# PSPS_AVNC_SRD_sensors-2020-09-29.net
KiCad netlist of a schematic drawn in EAGLE
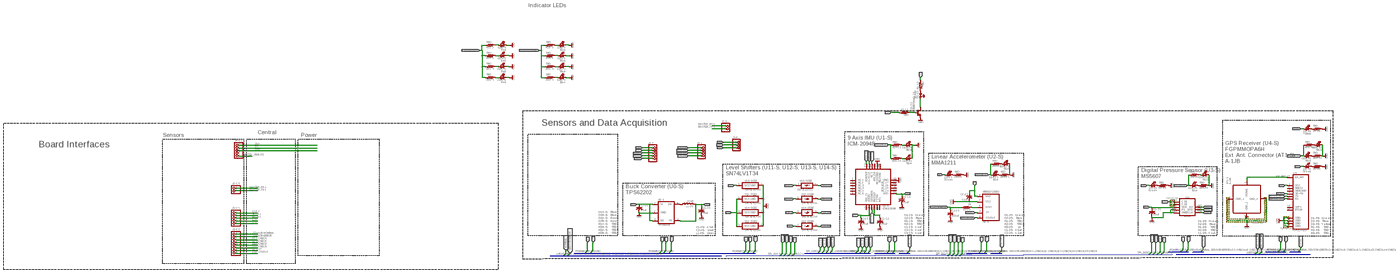
[diagram p0: schematic, sheet 1, overview]
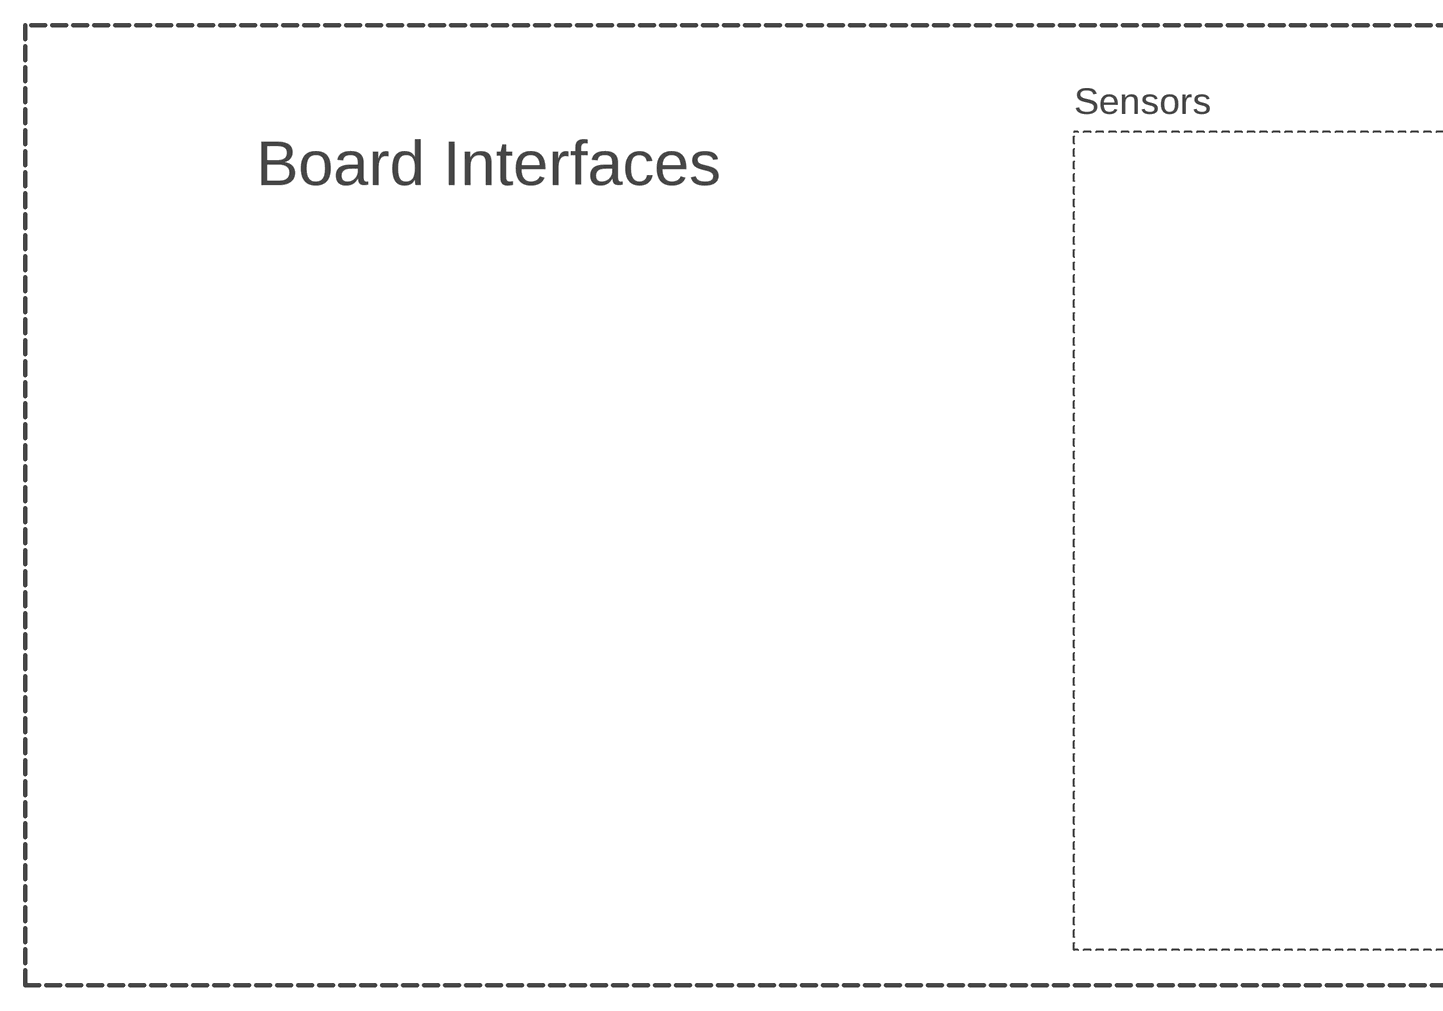
[diagram p1: schematic, sheet 1, part 1 of 4]
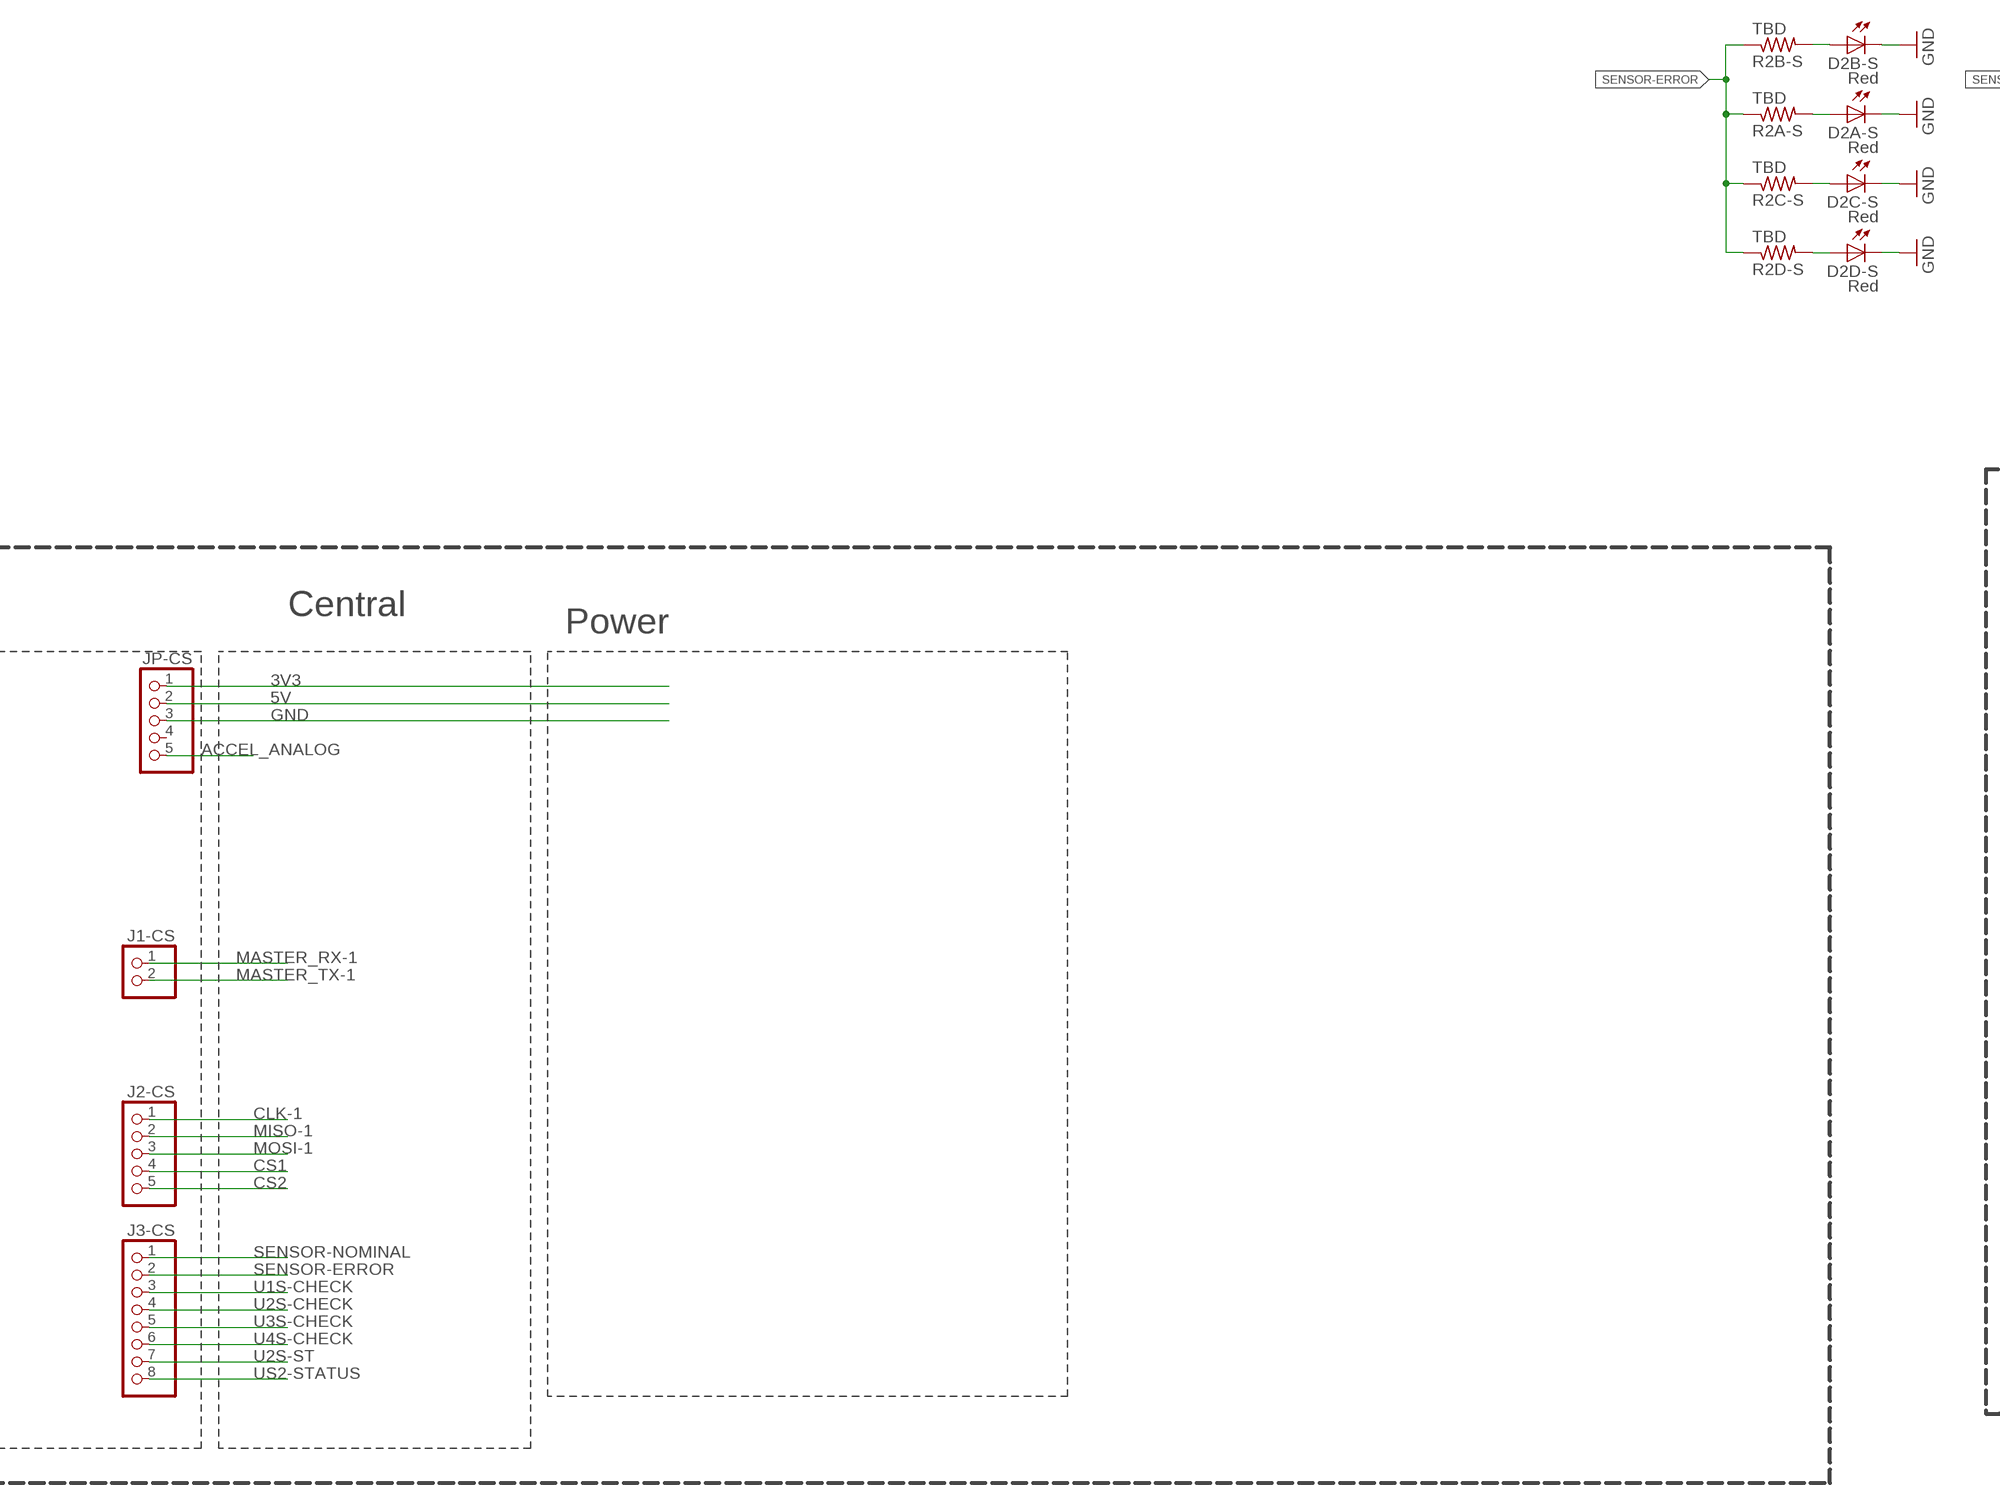
[diagram p2: schematic, sheet 1, part 2 of 4]
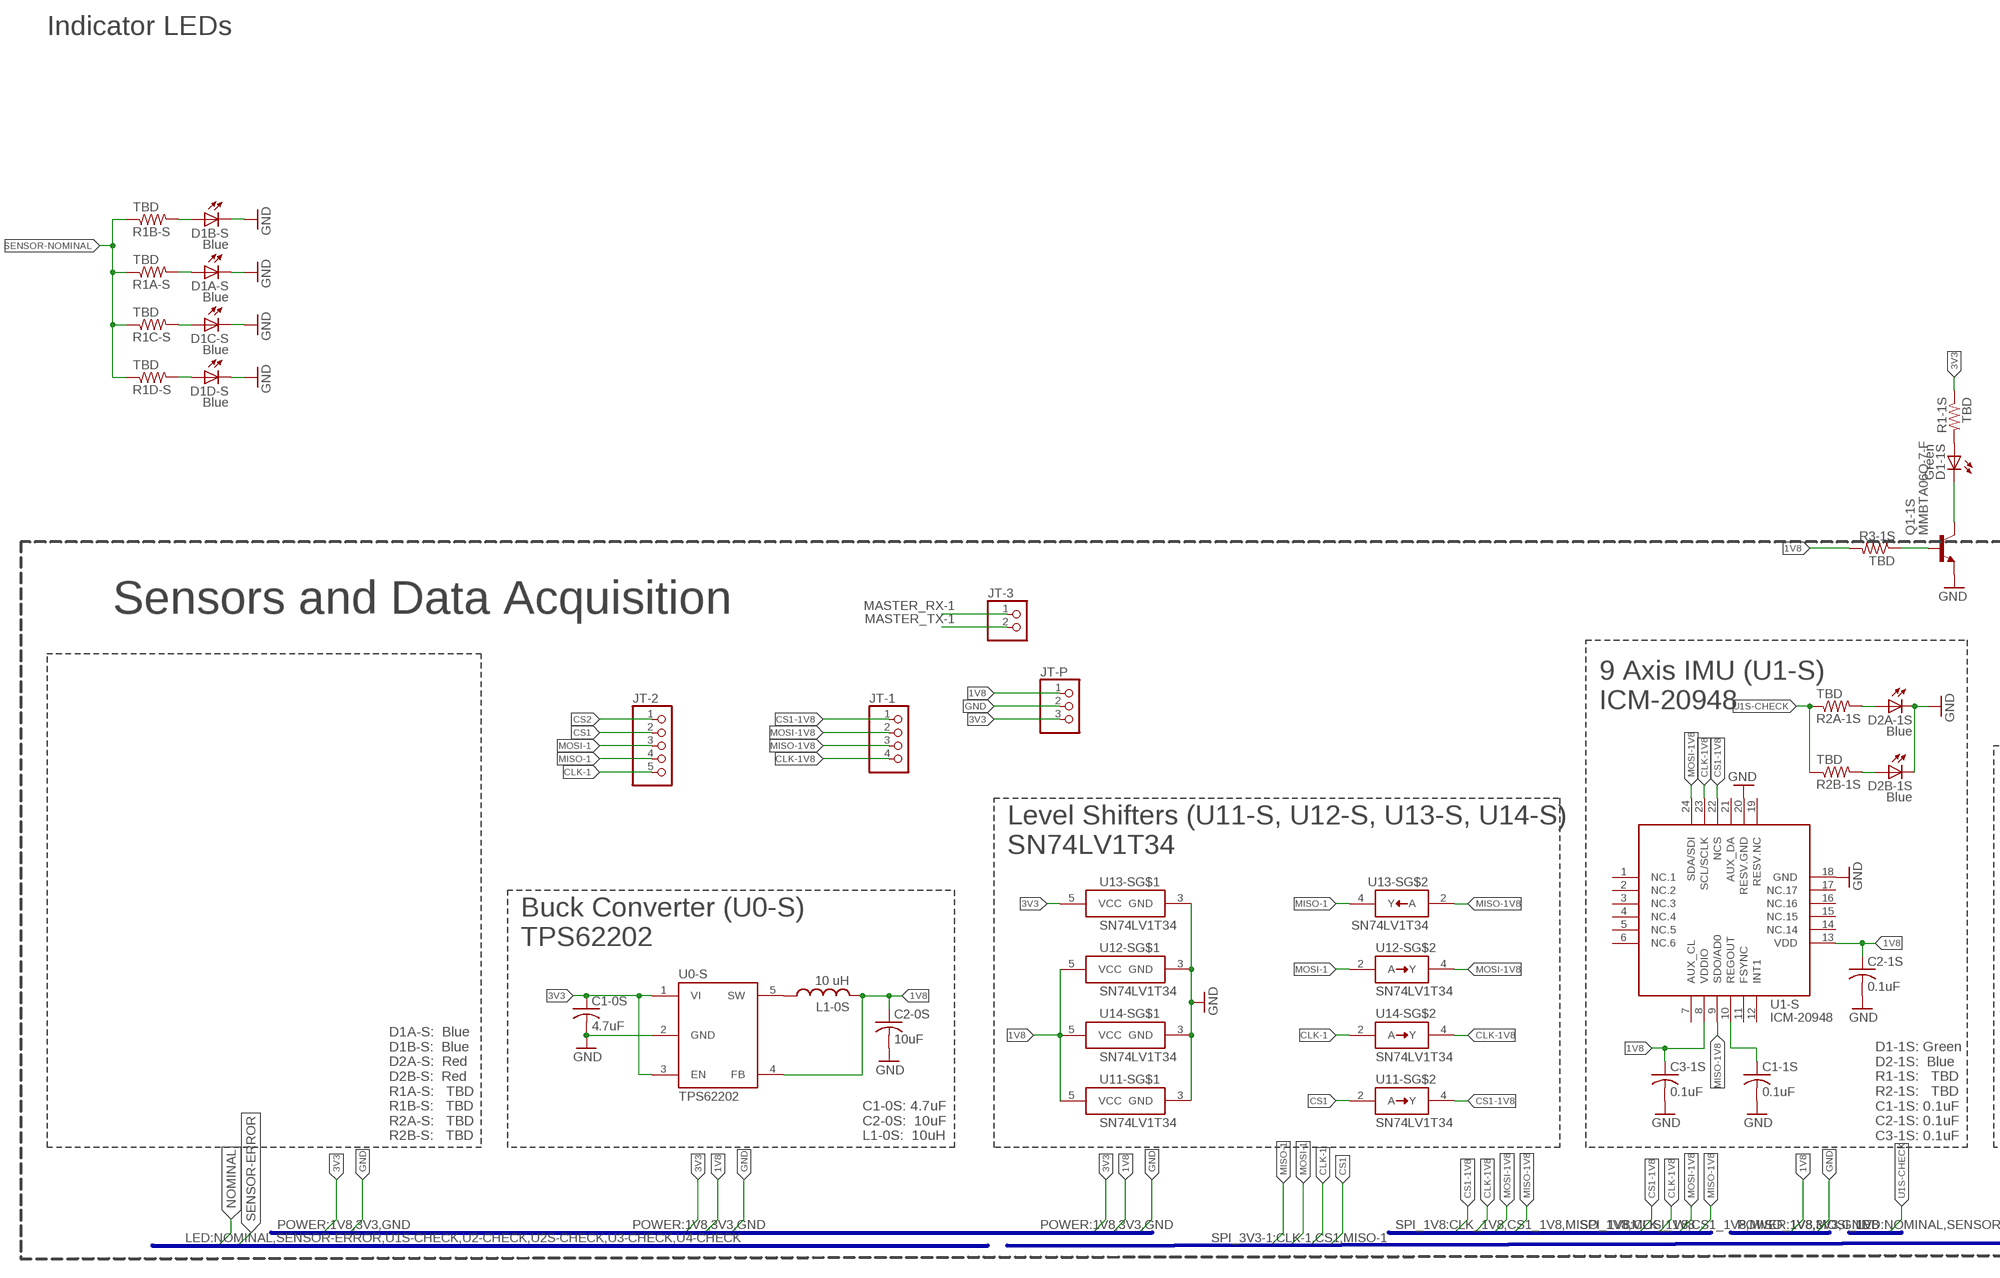
[diagram p3: schematic, sheet 1, part 3 of 4]
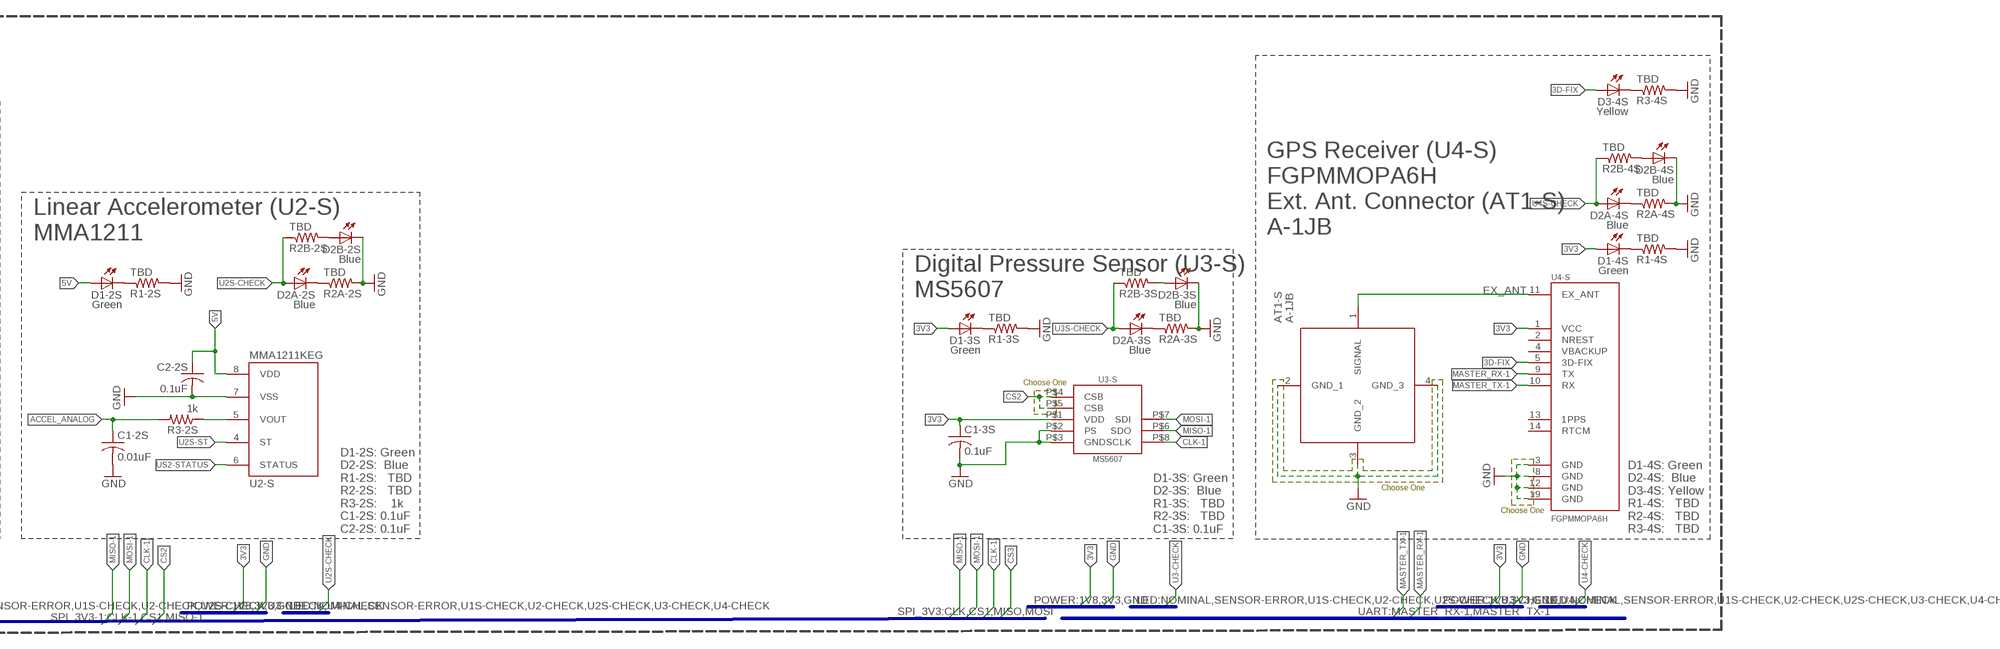
[diagram p4: schematic, sheet 1, part 4 of 4]

(export (version "E")
  (design (tool "Eeschema 10.0.6"))
  (components
    (comp (ref "AT1-S")
      (value "A-1JB")
      (footprint "eagle-import:A1JB")
      (fields (field (name "MOUSER_PART_NUMBER") "523-A-1JB"))
      (libsource (lib "eagle-import") (part "A-1JB"))
    )
    (comp (ref "C1-0S")
      (value "4.7uF")
      (footprint "eagle-import:C0805")
      (libsource (lib "eagle-import") (part "C-USC0805"))
    )
    (comp (ref "C1-1S")
      (value "0.1uF")
      (footprint "eagle-import:C0805")
      (libsource (lib "eagle-import") (part "C-USC0805"))
    )
    (comp (ref "C1-2S")
      (value "0.01uF")
      (footprint "eagle-import:C0805")
      (libsource (lib "eagle-import") (part "C-USC0805"))
    )
    (comp (ref "C1-3S")
      (value "0.1uF")
      (footprint "eagle-import:C0805")
      (libsource (lib "eagle-import") (part "C-USC0805"))
    )
    (comp (ref "C2-0S")
      (value "10uF")
      (footprint "eagle-import:C0805")
      (libsource (lib "eagle-import") (part "C-USC0805"))
    )
    (comp (ref "C2-1S")
      (value "0.1uF")
      (footprint "eagle-import:C0805")
      (libsource (lib "eagle-import") (part "C-USC0805"))
    )
    (comp (ref "C2-2S")
      (value "0.1uF")
      (footprint "eagle-import:C0805")
      (libsource (lib "eagle-import") (part "C-USC0805"))
    )
    (comp (ref "C3-1S")
      (value "0.1uF")
      (footprint "eagle-import:C0805")
      (libsource (lib "eagle-import") (part "C-USC0805"))
    )
    (comp (ref "D1-1S")
      (value "Green")
      (footprint "eagle-import:CHIPLED_0805")
      (libsource (lib "eagle-import") (part "LEDCHIPLED_0805"))
    )
    (comp (ref "D1-2S")
      (value "Green")
      (footprint "eagle-import:CHIPLED_0805")
      (libsource (lib "eagle-import") (part "LEDCHIPLED_0805"))
    )
    (comp (ref "D1-3S")
      (value "Green")
      (footprint "eagle-import:CHIPLED_0805")
      (libsource (lib "eagle-import") (part "LEDCHIPLED_0805"))
    )
    (comp (ref "D1-4S")
      (value "Green")
      (footprint "eagle-import:CHIPLED_0805")
      (libsource (lib "eagle-import") (part "LEDCHIPLED_0805"))
    )
    (comp (ref "D1A-S")
      (value "Blue")
      (footprint "eagle-import:CHIPLED_0805")
      (libsource (lib "eagle-import") (part "LEDCHIPLED_0805"))
    )
    (comp (ref "D1B-S")
      (value "Blue")
      (footprint "eagle-import:CHIPLED_0805")
      (libsource (lib "eagle-import") (part "LEDCHIPLED_0805"))
    )
    (comp (ref "D1C-S")
      (value "Blue")
      (footprint "eagle-import:CHIPLED_0805")
      (libsource (lib "eagle-import") (part "LEDCHIPLED_0805"))
    )
    (comp (ref "D1D-S")
      (value "Blue")
      (footprint "eagle-import:CHIPLED_0805")
      (libsource (lib "eagle-import") (part "LEDCHIPLED_0805"))
    )
    (comp (ref "D2A-1S")
      (value "Blue")
      (footprint "eagle-import:CHIPLED_0805")
      (libsource (lib "eagle-import") (part "LEDCHIPLED_0805"))
    )
    (comp (ref "D2A-2S")
      (value "Blue")
      (footprint "eagle-import:CHIPLED_0805")
      (libsource (lib "eagle-import") (part "LEDCHIPLED_0805"))
    )
    (comp (ref "D2A-3S")
      (value "Blue")
      (footprint "eagle-import:CHIPLED_0805")
      (libsource (lib "eagle-import") (part "LEDCHIPLED_0805"))
    )
    (comp (ref "D2A-4S")
      (value "Blue")
      (footprint "eagle-import:CHIPLED_0805")
      (libsource (lib "eagle-import") (part "LEDCHIPLED_0805"))
    )
    (comp (ref "D2A-S")
      (value "Red")
      (footprint "eagle-import:CHIPLED_0805")
      (libsource (lib "eagle-import") (part "LEDCHIPLED_0805"))
    )
    (comp (ref "D2B-1S")
      (value "Blue")
      (footprint "eagle-import:CHIPLED_0805")
      (libsource (lib "eagle-import") (part "LEDCHIPLED_0805"))
    )
    (comp (ref "D2B-2S")
      (value "Blue")
      (footprint "eagle-import:CHIPLED_0805")
      (libsource (lib "eagle-import") (part "LEDCHIPLED_0805"))
    )
    (comp (ref "D2B-3S")
      (value "Blue")
      (footprint "eagle-import:CHIPLED_0805")
      (libsource (lib "eagle-import") (part "LEDCHIPLED_0805"))
    )
    (comp (ref "D2B-4S")
      (value "Blue")
      (footprint "eagle-import:CHIPLED_0805")
      (libsource (lib "eagle-import") (part "LEDCHIPLED_0805"))
    )
    (comp (ref "D2B-S")
      (value "Red")
      (footprint "eagle-import:CHIPLED_0805")
      (libsource (lib "eagle-import") (part "LEDCHIPLED_0805"))
    )
    (comp (ref "D2C-S")
      (value "Red")
      (footprint "eagle-import:CHIPLED_0805")
      (libsource (lib "eagle-import") (part "LEDCHIPLED_0805"))
    )
    (comp (ref "D2D-S")
      (value "Red")
      (footprint "eagle-import:CHIPLED_0805")
      (libsource (lib "eagle-import") (part "LEDCHIPLED_0805"))
    )
    (comp (ref "D3-4S")
      (value "Yellow")
      (footprint "eagle-import:CHIPLED_0805")
      (libsource (lib "eagle-import") (part "LEDCHIPLED_0805"))
    )
    (comp (ref "J1-CS")
      (value "PINHD-1X2")
      (footprint "eagle-import:1X02")
      (libsource (lib "eagle-import") (part "PINHD-1X2"))
    )
    (comp (ref "J2-CS")
      (value "PINHD-1X5")
      (footprint "eagle-import:1X05")
      (libsource (lib "eagle-import") (part "PINHD-1X5"))
    )
    (comp (ref "J3-CS")
      (value "PINHD-1X8")
      (footprint "eagle-import:1X08")
      (libsource (lib "eagle-import") (part "PINHD-1X8"))
    )
    (comp (ref "JP-CS")
      (value "PINHD-1X5")
      (footprint "eagle-import:1X05")
      (libsource (lib "eagle-import") (part "PINHD-1X5"))
    )
    (comp (ref "JT-1")
      (value "PINHD-1X4")
      (footprint "eagle-import:1X04")
      (libsource (lib "eagle-import") (part "PINHD-1X4"))
    )
    (comp (ref "JT-2")
      (value "PINHD-1X5")
      (footprint "eagle-import:1X05")
      (libsource (lib "eagle-import") (part "PINHD-1X5"))
    )
    (comp (ref "JT-3")
      (value "PINHD-1X2")
      (footprint "eagle-import:1X02")
      (libsource (lib "eagle-import") (part "PINHD-1X2"))
    )
    (comp (ref "JT-P")
      (value "PINHD-1X3")
      (footprint "eagle-import:1X03")
      (libsource (lib "eagle-import") (part "PINHD-1X3"))
    )
    (comp (ref "L1-0S")
      (value "10 uH")
      (footprint "eagle-import:L1812")
      (libsource (lib "eagle-import") (part "L-USL1812"))
    )
    (comp (ref "Q1-1S")
      (value "MMBTA06Q-7-F")
      (footprint "eagle-import:SOT23")
      (libsource (lib "eagle-import") (part "NPN_TRANSISTOR"))
    )
    (comp (ref "R1-1S")
      (value "TBD")
      (footprint "eagle-import:R0805")
      (libsource (lib "eagle-import") (part "R-US_R0805"))
    )
    (comp (ref "R1-2S")
      (value "TBD")
      (footprint "eagle-import:R0805")
      (libsource (lib "eagle-import") (part "R-US_R0805"))
    )
    (comp (ref "R1-3S")
      (value "TBD")
      (footprint "eagle-import:R0805")
      (libsource (lib "eagle-import") (part "R-US_R0805"))
    )
    (comp (ref "R1-4S")
      (value "TBD")
      (footprint "eagle-import:R0805")
      (libsource (lib "eagle-import") (part "R-US_R0805"))
    )
    (comp (ref "R1A-S")
      (value "TBD")
      (footprint "eagle-import:R0805")
      (libsource (lib "eagle-import") (part "R-US_R0805"))
    )
    (comp (ref "R1B-S")
      (value "TBD")
      (footprint "eagle-import:R0805")
      (libsource (lib "eagle-import") (part "R-US_R0805"))
    )
    (comp (ref "R1C-S")
      (value "TBD")
      (footprint "eagle-import:R0805")
      (libsource (lib "eagle-import") (part "R-US_R0805"))
    )
    (comp (ref "R1D-S")
      (value "TBD")
      (footprint "eagle-import:R0805")
      (libsource (lib "eagle-import") (part "R-US_R0805"))
    )
    (comp (ref "R2A-1S")
      (value "TBD")
      (footprint "eagle-import:R0805")
      (libsource (lib "eagle-import") (part "R-US_R0805"))
    )
    (comp (ref "R2A-2S")
      (value "TBD")
      (footprint "eagle-import:R0805")
      (libsource (lib "eagle-import") (part "R-US_R0805"))
    )
    (comp (ref "R2A-3S")
      (value "TBD")
      (footprint "eagle-import:R0805")
      (libsource (lib "eagle-import") (part "R-US_R0805"))
    )
    (comp (ref "R2A-4S")
      (value "TBD")
      (footprint "eagle-import:R0805")
      (libsource (lib "eagle-import") (part "R-US_R0805"))
    )
    (comp (ref "R2A-S")
      (value "TBD")
      (footprint "eagle-import:R0805")
      (libsource (lib "eagle-import") (part "R-US_R0805"))
    )
    (comp (ref "R2B-1S")
      (value "TBD")
      (footprint "eagle-import:R0805")
      (libsource (lib "eagle-import") (part "R-US_R0805"))
    )
    (comp (ref "R2B-2S")
      (value "TBD")
      (footprint "eagle-import:R0805")
      (libsource (lib "eagle-import") (part "R-US_R0805"))
    )
    (comp (ref "R2B-3S")
      (value "TBD")
      (footprint "eagle-import:R0805")
      (libsource (lib "eagle-import") (part "R-US_R0805"))
    )
    (comp (ref "R2B-4S")
      (value "TBD")
      (footprint "eagle-import:R0805")
      (libsource (lib "eagle-import") (part "R-US_R0805"))
    )
    (comp (ref "R2B-S")
      (value "TBD")
      (footprint "eagle-import:R0805")
      (libsource (lib "eagle-import") (part "R-US_R0805"))
    )
    (comp (ref "R2C-S")
      (value "TBD")
      (footprint "eagle-import:R0805")
      (libsource (lib "eagle-import") (part "R-US_R0805"))
    )
    (comp (ref "R2D-S")
      (value "TBD")
      (footprint "eagle-import:R0805")
      (libsource (lib "eagle-import") (part "R-US_R0805"))
    )
    (comp (ref "R3-1S")
      (value "TBD")
      (footprint "eagle-import:R0805")
      (libsource (lib "eagle-import") (part "R-US_R0805"))
    )
    (comp (ref "R3-2S")
      (value "1k")
      (footprint "eagle-import:R0805")
      (libsource (lib "eagle-import") (part "R-US_R0805"))
    )
    (comp (ref "R3-4S")
      (value "TBD")
      (footprint "eagle-import:R0805")
      (libsource (lib "eagle-import") (part "R-US_R0805"))
    )
    (comp (ref "U0-S")
      (value "TPS62202")
      (footprint "eagle-import:SOT95P280X145-5")
      (libsource (lib "eagle-import") (part "TPS62202"))
    )
    (comp (ref "U1-S")
      (value "ICM-20948")
      (footprint "eagle-import:QFN40P300X300X105-25T159X175")
      (libsource (lib "eagle-import") (part "ICM-20948"))
    )
    (comp (ref "U2-S")
      (value "MMA1211KEG")
      (footprint "eagle-import:SOIC127P1041X355-16N")
      (libsource (lib "eagle-import") (part "MMA1211KEG"))
    )
    (comp (ref "U3-S")
      (value "MS5607")
      (footprint "eagle-import:MS5607")
      (libsource (lib "eagle-import") (part "MS5607"))
    )
    (comp (ref "U4-S")
      (value "FGPMMOPA6H")
      (footprint "eagle-import:SOIC127P1800X470-20N")
      (libsource (lib "eagle-import") (part "FGPMMOPA6H"))
    )
    (comp (ref "U11-S")
      (value "SN74LV1T34")
      (footprint "eagle-import:SOT65P210X110-5")
      (libsource (lib "eagle-import") (part "SN74LV1T34"))
    )
    (comp (ref "U12-S")
      (value "SN74LV1T34")
      (footprint "eagle-import:SOT65P210X110-5")
      (libsource (lib "eagle-import") (part "SN74LV1T34"))
    )
    (comp (ref "U13-S")
      (value "SN74LV1T34")
      (footprint "eagle-import:SOT65P210X110-5")
      (libsource (lib "eagle-import") (part "SN74LV1T34"))
    )
    (comp (ref "U14-S")
      (value "SN74LV1T34")
      (footprint "eagle-import:SOT65P210X110-5")
      (libsource (lib "eagle-import") (part "SN74LV1T34"))
    )
  )
  (nets
    (net (code "13") (name "/EX_ANT") (class "Default")
      (node (ref "AT1-S") (pin "1") (pinfunction "SIGNAL_1") (pintype "bidirectional"))
      (node (ref "U4-S") (pin "11") (pinfunction "EX_ANT_11") (pintype "bidirectional"))
    )
    (net (code "20") (name "1V8") (class "Default")
      (node (ref "C2-0S") (pin "1") (pinfunction "1_1") (pintype "passive"))
      (node (ref "C2-1S") (pin "1") (pinfunction "1_1") (pintype "passive"))
      (node (ref "C3-1S") (pin "1") (pinfunction "1_1") (pintype "passive"))
      (node (ref "JT-P") (pin "1") (pinfunction "1_1") (pintype "passive"))
      (node (ref "L1-0S") (pin "2") (pinfunction "2_2") (pintype "passive"))
      (node (ref "R3-1S") (pin "2") (pinfunction "2_2") (pintype "passive"))
      (node (ref "U0-S") (pin "4") (pinfunction "FB_4") (pintype "bidirectional"))
      (node (ref "U1-S") (pin "13") (pinfunction "VDD_13") (pintype "bidirectional"))
      (node (ref "U1-S") (pin "8") (pinfunction "VDDIO_8") (pintype "bidirectional"))
      (node (ref "U11-S") (pin "5") (pinfunction "VCC_5") (pintype "bidirectional"))
      (node (ref "U12-S") (pin "5") (pinfunction "VCC_5") (pintype "bidirectional"))
      (node (ref "U14-S") (pin "5") (pinfunction "VCC_5") (pintype "bidirectional"))
    )
    (net (code "21") (name "3D-FIX") (class "Default")
      (node (ref "D3-4S") (pin "A") (pinfunction "A_A") (pintype "passive"))
      (node (ref "U4-S") (pin "5") (pinfunction "3D-FIX_5") (pintype "bidirectional"))
    )
    (net (code "22") (name "3V3") (class "Default")
      (node (ref "C1-0S") (pin "1") (pinfunction "1_1") (pintype "passive"))
      (node (ref "C1-3S") (pin "1") (pinfunction "1_1") (pintype "passive"))
      (node (ref "D1-3S") (pin "A") (pinfunction "A_A") (pintype "passive"))
      (node (ref "D1-4S") (pin "A") (pinfunction "A_A") (pintype "passive"))
      (node (ref "JP-CS") (pin "1") (pinfunction "1_1") (pintype "passive"))
      (node (ref "JT-P") (pin "3") (pinfunction "3_3") (pintype "passive"))
      (node (ref "R1-1S") (pin "1") (pinfunction "1_1") (pintype "passive"))
      (node (ref "U0-S") (pin "1") (pinfunction "VI_1") (pintype "bidirectional"))
      (node (ref "U0-S") (pin "3") (pinfunction "EN_3") (pintype "bidirectional"))
      (node (ref "U13-S") (pin "5") (pinfunction "VCC_5") (pintype "bidirectional"))
      (node (ref "U3-S") (pin "P$1") (pinfunction "VDD_P$1") (pintype "bidirectional"))
      (node (ref "U4-S") (pin "1") (pinfunction "VCC_1") (pintype "bidirectional"))
    )
    (net (code "23") (name "5V") (class "Default")
      (node (ref "C2-2S") (pin "1") (pinfunction "1_1") (pintype "passive"))
      (node (ref "D1-2S") (pin "A") (pinfunction "A_A") (pintype "passive"))
      (node (ref "JP-CS") (pin "2") (pinfunction "2_2") (pintype "passive"))
      (node (ref "U2-S") (pin "8") (pinfunction "VDD_8") (pintype "bidirectional"))
    )
    (net (code "24") (name "ACCEL_ANALOG") (class "Default")
      (node (ref "C1-2S") (pin "1") (pinfunction "1_1") (pintype "passive"))
      (node (ref "JP-CS") (pin "5") (pinfunction "5_5") (pintype "passive"))
      (node (ref "R3-2S") (pin "2") (pinfunction "2_2") (pintype "passive"))
    )
    (net (code "25") (name "CLK-1") (class "Default")
      (node (ref "J2-CS") (pin "1") (pinfunction "1_1") (pintype "passive"))
      (node (ref "JT-2") (pin "5") (pinfunction "5_5") (pintype "passive"))
      (node (ref "U14-S") (pin "2") (pinfunction "A_2") (pintype "bidirectional"))
      (node (ref "U3-S") (pin "P$8") (pinfunction "SCLK_P$8") (pintype "bidirectional"))
    )
    (net (code "26") (name "CLK-1V8") (class "Default")
      (node (ref "JT-1") (pin "4") (pinfunction "4_4") (pintype "passive"))
      (node (ref "U1-S") (pin "23") (pinfunction "SCL/SCLK_23") (pintype "bidirectional"))
      (node (ref "U14-S") (pin "4") (pinfunction "Y_4") (pintype "bidirectional"))
    )
    (net (code "27") (name "CS1") (class "Default")
      (node (ref "J2-CS") (pin "4") (pinfunction "4_4") (pintype "passive"))
      (node (ref "JT-2") (pin "2") (pinfunction "2_2") (pintype "passive"))
      (node (ref "U11-S") (pin "2") (pinfunction "A_2") (pintype "bidirectional"))
    )
    (net (code "28") (name "CS1-1V8") (class "Default")
      (node (ref "JT-1") (pin "1") (pinfunction "1_1") (pintype "passive"))
      (node (ref "U1-S") (pin "22") (pinfunction "NCS_22") (pintype "bidirectional"))
      (node (ref "U11-S") (pin "4") (pinfunction "Y_4") (pintype "bidirectional"))
    )
    (net (code "29") (name "CS2") (class "Default")
      (node (ref "J2-CS") (pin "5") (pinfunction "5_5") (pintype "passive"))
      (node (ref "JT-2") (pin "1") (pinfunction "1_1") (pintype "passive"))
      (node (ref "U3-S") (pin "P$4") (pinfunction "CSB_P$4") (pintype "bidirectional"))
      (node (ref "U3-S") (pin "P$5") (pinfunction "CSB_P$5") (pintype "bidirectional"))
    )
    (net (code "31") (name "GND") (class "Default")
      (node (ref "AT1-S") (pin "2") (pinfunction "GND_1_2") (pintype "bidirectional"))
      (node (ref "AT1-S") (pin "3") (pinfunction "GND_2_3") (pintype "bidirectional"))
      (node (ref "AT1-S") (pin "4") (pinfunction "GND_3_4") (pintype "bidirectional"))
      (node (ref "C1-0S") (pin "2") (pinfunction "2_2") (pintype "passive"))
      (node (ref "C1-1S") (pin "2") (pinfunction "2_2") (pintype "passive"))
      (node (ref "C1-2S") (pin "2") (pinfunction "2_2") (pintype "passive"))
      (node (ref "C1-3S") (pin "2") (pinfunction "2_2") (pintype "passive"))
      (node (ref "C2-0S") (pin "2") (pinfunction "2_2") (pintype "passive"))
      (node (ref "C2-1S") (pin "2") (pinfunction "2_2") (pintype "passive"))
      (node (ref "C2-2S") (pin "2") (pinfunction "2_2") (pintype "passive"))
      (node (ref "C3-1S") (pin "2") (pinfunction "2_2") (pintype "passive"))
      (node (ref "D1A-S") (pin "C") (pinfunction "C_C") (pintype "passive"))
      (node (ref "D1B-S") (pin "C") (pinfunction "C_C") (pintype "passive"))
      (node (ref "D1C-S") (pin "C") (pinfunction "C_C") (pintype "passive"))
      (node (ref "D1D-S") (pin "C") (pinfunction "C_C") (pintype "passive"))
      (node (ref "D2A-1S") (pin "C") (pinfunction "C_C") (pintype "passive"))
      (node (ref "D2A-S") (pin "C") (pinfunction "C_C") (pintype "passive"))
      (node (ref "D2B-1S") (pin "C") (pinfunction "C_C") (pintype "passive"))
      (node (ref "D2B-2S") (pin "C") (pinfunction "C_C") (pintype "passive"))
      (node (ref "D2B-3S") (pin "C") (pinfunction "C_C") (pintype "passive"))
      (node (ref "D2B-4S") (pin "C") (pinfunction "C_C") (pintype "passive"))
      (node (ref "D2B-S") (pin "C") (pinfunction "C_C") (pintype "passive"))
      (node (ref "D2C-S") (pin "C") (pinfunction "C_C") (pintype "passive"))
      (node (ref "D2D-S") (pin "C") (pinfunction "C_C") (pintype "passive"))
      (node (ref "JP-CS") (pin "3") (pinfunction "3_3") (pintype "passive"))
      (node (ref "JT-P") (pin "2") (pinfunction "2_2") (pintype "passive"))
      (node (ref "Q1-1S") (pin "3") (pinfunction "E_3") (pintype "passive"))
      (node (ref "R1-2S") (pin "2") (pinfunction "2_2") (pintype "passive"))
      (node (ref "R1-3S") (pin "2") (pinfunction "2_2") (pintype "passive"))
      (node (ref "R1-4S") (pin "2") (pinfunction "2_2") (pintype "passive"))
      (node (ref "R2A-2S") (pin "2") (pinfunction "2_2") (pintype "passive"))
      (node (ref "R2A-3S") (pin "2") (pinfunction "2_2") (pintype "passive"))
      (node (ref "R2A-4S") (pin "2") (pinfunction "2_2") (pintype "passive"))
      (node (ref "R3-4S") (pin "2") (pinfunction "2_2") (pintype "passive"))
      (node (ref "U0-S") (pin "2") (pinfunction "GND_2") (pintype "bidirectional"))
      (node (ref "U1-S") (pin "18") (pinfunction "GND_18") (pintype "bidirectional"))
      (node (ref "U1-S") (pin "20") (pinfunction "RESV.GND_20") (pintype "bidirectional"))
      (node (ref "U11-S") (pin "3") (pinfunction "GND_3") (pintype "bidirectional"))
      (node (ref "U12-S") (pin "3") (pinfunction "GND_3") (pintype "bidirectional"))
      (node (ref "U13-S") (pin "3") (pinfunction "GND_3") (pintype "bidirectional"))
      (node (ref "U14-S") (pin "3") (pinfunction "GND_3") (pintype "bidirectional"))
      (node (ref "U2-S") (pin "7") (pinfunction "VSS_7") (pintype "bidirectional"))
      (node (ref "U3-S") (pin "P$2") (pinfunction "PS_P$2") (pintype "bidirectional"))
      (node (ref "U3-S") (pin "P$3") (pinfunction "GND_P$3") (pintype "bidirectional"))
      (node (ref "U4-S") (pin "12") (pinfunction "GND_12") (pintype "bidirectional"))
      (node (ref "U4-S") (pin "19") (pinfunction "GND_19") (pintype "bidirectional"))
      (node (ref "U4-S") (pin "3") (pinfunction "GND_3") (pintype "bidirectional"))
      (node (ref "U4-S") (pin "8") (pinfunction "GND_8") (pintype "bidirectional"))
    )
    (net (code "32") (name "MASTER_RX-1") (class "Default")
      (node (ref "J1-CS") (pin "1") (pinfunction "1_1") (pintype "passive"))
      (node (ref "JT-3") (pin "1") (pinfunction "1_1") (pintype "passive"))
      (node (ref "U4-S") (pin "9") (pinfunction "TX_9") (pintype "bidirectional"))
    )
    (net (code "33") (name "MASTER_TX-1") (class "Default")
      (node (ref "J1-CS") (pin "2") (pinfunction "2_2") (pintype "passive"))
      (node (ref "JT-3") (pin "2") (pinfunction "2_2") (pintype "passive"))
      (node (ref "U4-S") (pin "10") (pinfunction "RX_10") (pintype "bidirectional"))
    )
    (net (code "34") (name "MISO-1") (class "Default")
      (node (ref "J2-CS") (pin "2") (pinfunction "2_2") (pintype "passive"))
      (node (ref "JT-2") (pin "4") (pinfunction "4_4") (pintype "passive"))
      (node (ref "U13-S") (pin "4") (pinfunction "Y_4") (pintype "bidirectional"))
      (node (ref "U3-S") (pin "P$6") (pinfunction "SDO_P$6") (pintype "bidirectional"))
    )
    (net (code "35") (name "MISO-1V8") (class "Default")
      (node (ref "JT-1") (pin "3") (pinfunction "3_3") (pintype "passive"))
      (node (ref "U1-S") (pin "9") (pinfunction "SDO/AD0_9") (pintype "bidirectional"))
      (node (ref "U13-S") (pin "2") (pinfunction "A_2") (pintype "bidirectional"))
    )
    (net (code "36") (name "MOSI-1") (class "Default")
      (node (ref "J2-CS") (pin "3") (pinfunction "3_3") (pintype "passive"))
      (node (ref "JT-2") (pin "3") (pinfunction "3_3") (pintype "passive"))
      (node (ref "U12-S") (pin "2") (pinfunction "A_2") (pintype "bidirectional"))
      (node (ref "U3-S") (pin "P$7") (pinfunction "SDI_P$7") (pintype "bidirectional"))
    )
    (net (code "37") (name "MOSI-1V8") (class "Default")
      (node (ref "JT-1") (pin "2") (pinfunction "2_2") (pintype "passive"))
      (node (ref "U1-S") (pin "24") (pinfunction "SDA/SDI_24") (pintype "bidirectional"))
      (node (ref "U12-S") (pin "4") (pinfunction "Y_4") (pintype "bidirectional"))
    )
    (net (code "39") (name "Net-(D1-1S-PadA)") (class "Default")
      (node (ref "D1-1S") (pin "A") (pinfunction "A_A") (pintype "passive"))
      (node (ref "R1-1S") (pin "2") (pinfunction "2_2") (pintype "passive"))
    )
    (net (code "40") (name "Net-(D1-2S-PadC)") (class "Default")
      (node (ref "D1-2S") (pin "C") (pinfunction "C_C") (pintype "passive"))
      (node (ref "R1-2S") (pin "1") (pinfunction "1_1") (pintype "passive"))
    )
    (net (code "41") (name "Net-(D1-3S-PadC)") (class "Default")
      (node (ref "D1-3S") (pin "C") (pinfunction "C_C") (pintype "passive"))
      (node (ref "R1-3S") (pin "1") (pinfunction "1_1") (pintype "passive"))
    )
    (net (code "42") (name "Net-(D1-4S-PadC)") (class "Default")
      (node (ref "D1-4S") (pin "C") (pinfunction "C_C") (pintype "passive"))
      (node (ref "R1-4S") (pin "1") (pinfunction "1_1") (pintype "passive"))
    )
    (net (code "43") (name "Net-(D1A-S-PadA)") (class "Default")
      (node (ref "D1A-S") (pin "A") (pinfunction "A_A") (pintype "passive"))
      (node (ref "R1A-S") (pin "2") (pinfunction "2_2") (pintype "passive"))
    )
    (net (code "44") (name "Net-(D1B-S-PadA)") (class "Default")
      (node (ref "D1B-S") (pin "A") (pinfunction "A_A") (pintype "passive"))
      (node (ref "R1B-S") (pin "2") (pinfunction "2_2") (pintype "passive"))
    )
    (net (code "45") (name "Net-(D1C-S-PadA)") (class "Default")
      (node (ref "D1C-S") (pin "A") (pinfunction "A_A") (pintype "passive"))
      (node (ref "R1C-S") (pin "2") (pinfunction "2_2") (pintype "passive"))
    )
    (net (code "46") (name "Net-(D1D-S-PadA)") (class "Default")
      (node (ref "D1D-S") (pin "A") (pinfunction "A_A") (pintype "passive"))
      (node (ref "R1D-S") (pin "2") (pinfunction "2_2") (pintype "passive"))
    )
    (net (code "47") (name "Net-(D2A-1S-PadA)") (class "Default")
      (node (ref "D2A-1S") (pin "A") (pinfunction "A_A") (pintype "passive"))
      (node (ref "R2A-1S") (pin "2") (pinfunction "2_2") (pintype "passive"))
    )
    (net (code "48") (name "Net-(D2A-2S-PadC)") (class "Default")
      (node (ref "D2A-2S") (pin "C") (pinfunction "C_C") (pintype "passive"))
      (node (ref "R2A-2S") (pin "1") (pinfunction "1_1") (pintype "passive"))
    )
    (net (code "49") (name "Net-(D2A-3S-PadC)") (class "Default")
      (node (ref "D2A-3S") (pin "C") (pinfunction "C_C") (pintype "passive"))
      (node (ref "R2A-3S") (pin "1") (pinfunction "1_1") (pintype "passive"))
    )
    (net (code "50") (name "Net-(D2A-4S-PadC)") (class "Default")
      (node (ref "D2A-4S") (pin "C") (pinfunction "C_C") (pintype "passive"))
      (node (ref "R2A-4S") (pin "1") (pinfunction "1_1") (pintype "passive"))
    )
    (net (code "51") (name "Net-(D2A-S-PadA)") (class "Default")
      (node (ref "D2A-S") (pin "A") (pinfunction "A_A") (pintype "passive"))
      (node (ref "R2A-S") (pin "2") (pinfunction "2_2") (pintype "passive"))
    )
    (net (code "52") (name "Net-(D2B-1S-PadA)") (class "Default")
      (node (ref "D2B-1S") (pin "A") (pinfunction "A_A") (pintype "passive"))
      (node (ref "R2B-1S") (pin "2") (pinfunction "2_2") (pintype "passive"))
    )
    (net (code "53") (name "Net-(D2B-2S-PadA)") (class "Default")
      (node (ref "D2B-2S") (pin "A") (pinfunction "A_A") (pintype "passive"))
      (node (ref "R2B-2S") (pin "2") (pinfunction "2_2") (pintype "passive"))
    )
    (net (code "54") (name "Net-(D2B-3S-PadA)") (class "Default")
      (node (ref "D2B-3S") (pin "A") (pinfunction "A_A") (pintype "passive"))
      (node (ref "R2B-3S") (pin "2") (pinfunction "2_2") (pintype "passive"))
    )
    (net (code "55") (name "Net-(D2B-4S-PadA)") (class "Default")
      (node (ref "D2B-4S") (pin "A") (pinfunction "A_A") (pintype "passive"))
      (node (ref "R2B-4S") (pin "2") (pinfunction "2_2") (pintype "passive"))
    )
    (net (code "56") (name "Net-(D2B-S-PadA)") (class "Default")
      (node (ref "D2B-S") (pin "A") (pinfunction "A_A") (pintype "passive"))
      (node (ref "R2B-S") (pin "2") (pinfunction "2_2") (pintype "passive"))
    )
    (net (code "57") (name "Net-(D2C-S-PadA)") (class "Default")
      (node (ref "D2C-S") (pin "A") (pinfunction "A_A") (pintype "passive"))
      (node (ref "R2C-S") (pin "2") (pinfunction "2_2") (pintype "passive"))
    )
    (net (code "58") (name "Net-(D2D-S-PadA)") (class "Default")
      (node (ref "D2D-S") (pin "A") (pinfunction "A_A") (pintype "passive"))
      (node (ref "R2D-S") (pin "2") (pinfunction "2_2") (pintype "passive"))
    )
    (net (code "59") (name "Net-(D3-4S-PadC)") (class "Default")
      (node (ref "D3-4S") (pin "C") (pinfunction "C_C") (pintype "passive"))
      (node (ref "R3-4S") (pin "1") (pinfunction "1_1") (pintype "passive"))
    )
    (net (code "60") (name "Net-(Q1-1S-B)") (class "Default")
      (node (ref "Q1-1S") (pin "1") (pinfunction "B_1") (pintype "passive"))
      (node (ref "R3-1S") (pin "1") (pinfunction "1_1") (pintype "passive"))
    )
    (net (code "61") (name "Net-(Q1-1S-C)") (class "Default")
      (node (ref "D1-1S") (pin "C") (pinfunction "C_C") (pintype "passive"))
      (node (ref "Q1-1S") (pin "2") (pinfunction "C_2") (pintype "passive"))
    )
    (net (code "62") (name "Net-(U0-S-SW)") (class "Default")
      (node (ref "L1-0S") (pin "1") (pinfunction "1_1") (pintype "passive"))
      (node (ref "U0-S") (pin "5") (pinfunction "SW_5") (pintype "bidirectional"))
    )
    (net (code "63") (name "Net-(U1-S-REGOUT)") (class "Default")
      (node (ref "C1-1S") (pin "1") (pinfunction "1_1") (pintype "passive"))
      (node (ref "U1-S") (pin "10") (pinfunction "REGOUT_10") (pintype "bidirectional"))
    )
    (net (code "64") (name "Net-(U2-S-VOUT)") (class "Default")
      (node (ref "R3-2S") (pin "1") (pinfunction "1_1") (pintype "passive"))
      (node (ref "U2-S") (pin "5") (pinfunction "VOUT_5") (pintype "bidirectional"))
    )
    (net (code "65") (name "SENSOR-ERROR") (class "Default")
      (node (ref "J3-CS") (pin "2") (pinfunction "2_2") (pintype "passive"))
      (node (ref "R2A-S") (pin "1") (pinfunction "1_1") (pintype "passive"))
      (node (ref "R2B-S") (pin "1") (pinfunction "1_1") (pintype "passive"))
      (node (ref "R2C-S") (pin "1") (pinfunction "1_1") (pintype "passive"))
      (node (ref "R2D-S") (pin "1") (pinfunction "1_1") (pintype "passive"))
    )
    (net (code "66") (name "SENSOR-NOMINAL") (class "Default")
      (node (ref "J3-CS") (pin "1") (pinfunction "1_1") (pintype "passive"))
      (node (ref "R1A-S") (pin "1") (pinfunction "1_1") (pintype "passive"))
      (node (ref "R1B-S") (pin "1") (pinfunction "1_1") (pintype "passive"))
      (node (ref "R1C-S") (pin "1") (pinfunction "1_1") (pintype "passive"))
      (node (ref "R1D-S") (pin "1") (pinfunction "1_1") (pintype "passive"))
    )
    (net (code "67") (name "U1S-CHECK") (class "Default")
      (node (ref "J3-CS") (pin "3") (pinfunction "3_3") (pintype "passive"))
      (node (ref "R2A-1S") (pin "1") (pinfunction "1_1") (pintype "passive"))
      (node (ref "R2B-1S") (pin "1") (pinfunction "1_1") (pintype "passive"))
    )
    (net (code "68") (name "U2S-CHECK") (class "Default")
      (node (ref "D2A-2S") (pin "A") (pinfunction "A_A") (pintype "passive"))
      (node (ref "J3-CS") (pin "4") (pinfunction "4_4") (pintype "passive"))
      (node (ref "R2B-2S") (pin "1") (pinfunction "1_1") (pintype "passive"))
    )
    (net (code "69") (name "U2S-ST") (class "Default")
      (node (ref "J3-CS") (pin "7") (pinfunction "7_7") (pintype "passive"))
      (node (ref "U2-S") (pin "4") (pinfunction "ST_4") (pintype "bidirectional"))
    )
    (net (code "71") (name "U3S-CHECK") (class "Default")
      (node (ref "D2A-3S") (pin "A") (pinfunction "A_A") (pintype "passive"))
      (node (ref "J3-CS") (pin "5") (pinfunction "5_5") (pintype "passive"))
      (node (ref "R2B-3S") (pin "1") (pinfunction "1_1") (pintype "passive"))
    )
    (net (code "73") (name "U4S-CHECK") (class "Default")
      (node (ref "D2A-4S") (pin "A") (pinfunction "A_A") (pintype "passive"))
      (node (ref "J3-CS") (pin "6") (pinfunction "6_6") (pintype "passive"))
      (node (ref "R2B-4S") (pin "1") (pinfunction "1_1") (pintype "passive"))
    )
    (net (code "74") (name "US2-STATUS") (class "Default")
      (node (ref "J3-CS") (pin "8") (pinfunction "8_8") (pintype "passive"))
      (node (ref "U2-S") (pin "6") (pinfunction "STATUS_6") (pintype "bidirectional"))
    )
    (net (code "75") (name "unconnected-(JP-CS-Pad4)") (class "Default")
      (node (ref "JP-CS") (pin "4") (pinfunction "4_4") (pintype "passive"))
    )
    (net (code "76") (name "unconnected-(U1-S-AUX_CL-Pad7)") (class "Default")
      (node (ref "U1-S") (pin "7") (pinfunction "AUX_CL_7") (pintype "bidirectional"))
    )
    (net (code "77") (name "unconnected-(U1-S-AUX_DA-Pad21)") (class "Default")
      (node (ref "U1-S") (pin "21") (pinfunction "AUX_DA_21") (pintype "bidirectional"))
    )
    (net (code "78") (name "unconnected-(U1-S-FSYNC-Pad11)") (class "Default")
      (node (ref "U1-S") (pin "11") (pinfunction "FSYNC_11") (pintype "bidirectional"))
    )
    (net (code "79") (name "unconnected-(U1-S-INT1-Pad12)") (class "Default")
      (node (ref "U1-S") (pin "12") (pinfunction "INT1_12") (pintype "bidirectional"))
    )
    (net (code "80") (name "unconnected-(U1-S-NC.1-Pad1)") (class "Default")
      (node (ref "U1-S") (pin "1") (pinfunction "NC.1_1") (pintype "bidirectional"))
    )
    (net (code "81") (name "unconnected-(U1-S-NC.2-Pad2)") (class "Default")
      (node (ref "U1-S") (pin "2") (pinfunction "NC.2_2") (pintype "bidirectional"))
    )
    (net (code "82") (name "unconnected-(U1-S-NC.3-Pad3)") (class "Default")
      (node (ref "U1-S") (pin "3") (pinfunction "NC.3_3") (pintype "bidirectional"))
    )
    (net (code "83") (name "unconnected-(U1-S-NC.4-Pad4)") (class "Default")
      (node (ref "U1-S") (pin "4") (pinfunction "NC.4_4") (pintype "bidirectional"))
    )
    (net (code "84") (name "unconnected-(U1-S-NC.5-Pad5)") (class "Default")
      (node (ref "U1-S") (pin "5") (pinfunction "NC.5_5") (pintype "bidirectional"))
    )
    (net (code "85") (name "unconnected-(U1-S-NC.6-Pad6)") (class "Default")
      (node (ref "U1-S") (pin "6") (pinfunction "NC.6_6") (pintype "bidirectional"))
    )
    (net (code "86") (name "unconnected-(U1-S-NC.14-Pad14)") (class "Default")
      (node (ref "U1-S") (pin "14") (pinfunction "NC.14_14") (pintype "bidirectional"))
    )
    (net (code "87") (name "unconnected-(U1-S-NC.15-Pad15)") (class "Default")
      (node (ref "U1-S") (pin "15") (pinfunction "NC.15_15") (pintype "bidirectional"))
    )
    (net (code "88") (name "unconnected-(U1-S-NC.16-Pad16)") (class "Default")
      (node (ref "U1-S") (pin "16") (pinfunction "NC.16_16") (pintype "bidirectional"))
    )
    (net (code "89") (name "unconnected-(U1-S-NC.17-Pad17)") (class "Default")
      (node (ref "U1-S") (pin "17") (pinfunction "NC.17_17") (pintype "bidirectional"))
    )
    (net (code "90") (name "unconnected-(U1-S-RESV.NC-Pad19)") (class "Default")
      (node (ref "U1-S") (pin "19") (pinfunction "RESV.NC_19") (pintype "bidirectional"))
    )
    (net (code "91") (name "unconnected-(U4-S-1PPS-Pad13)") (class "Default")
      (node (ref "U4-S") (pin "13") (pinfunction "1PPS_13") (pintype "bidirectional"))
    )
    (net (code "92") (name "unconnected-(U4-S-NREST-Pad2)") (class "Default")
      (node (ref "U4-S") (pin "2") (pinfunction "NREST_2") (pintype "bidirectional"))
    )
    (net (code "93") (name "unconnected-(U4-S-RTCM-Pad14)") (class "Default")
      (node (ref "U4-S") (pin "14") (pinfunction "RTCM_14") (pintype "bidirectional"))
    )
    (net (code "94") (name "unconnected-(U4-S-VBACKUP-Pad4)") (class "Default")
      (node (ref "U4-S") (pin "4") (pinfunction "VBACKUP_4") (pintype "bidirectional"))
    )
  )
)
